# POWER.net
KiCad netlist of a schematic drawn in Altium Designer
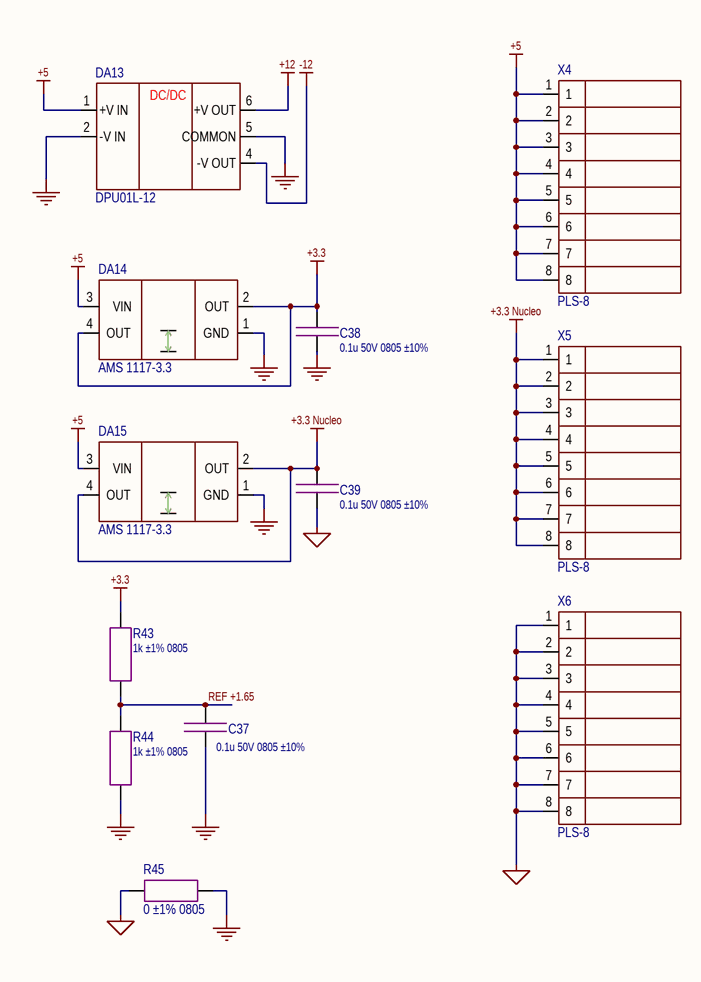
[diagram p0: POWER.SchDoc]

(export (version "E")
  (design (tool "Eeschema 10.0.6"))
  (components
    (comp (ref "C37")
      (value "0.1u 50V 0805 ±10%")
      (footprint "CAP: SMD 0805 MD IPC 782")
      (libsource (lib "UOMP capacitors") (part "0.1u 50V 0805 ±10%"))
    )
    (comp (ref "C38")
      (value "0.1u 50V 0805 ±10%")
      (footprint "CAP: SMD 0805 MD IPC 782")
      (libsource (lib "UOMP capacitors") (part "0.1u 50V 0805 ±10%"))
    )
    (comp (ref "C39")
      (value "0.1u 50V 0805 ±10%")
      (footprint "CAP: SMD 0805 MD IPC 782")
      (libsource (lib "UOMP capacitors") (part "0.1u 50V 0805 ±10%"))
    )
    (comp (ref "DA13")
      (value "DPU01L-12")
      (footprint "SIP-6")
      (libsource (lib "UOMP power") (part "DC-DC{colon} +12/-12V DPU01L-12"))
    )
    (comp (ref "DA14")
      (value "AMS 1117-3.3")
      (footprint "IC: SOT 223")
      (libsource (lib "UOMP power") (part "LDO{colon} 15-3.3V AMS1117"))
    )
    (comp (ref "DA15")
      (value "AMS 1117-3.3")
      (footprint "IC: SOT 223")
      (libsource (lib "UOMP power") (part "LDO{colon} 15-3.3V AMS1117"))
    )
    (comp (ref "R43")
      (value "1k ±1% 0805")
      (footprint "RES: SMD 0805 MD IPC 782")
      (libsource (lib "UOMP resistors") (part "1k ±1% 0805"))
    )
    (comp (ref "R44")
      (value "1k ±1% 0805")
      (footprint "RES: SMD 0805 MD IPC 782")
      (libsource (lib "UOMP resistors") (part "1k ±1% 0805"))
    )
    (comp (ref "R45")
      (value "0 ±1% 0805")
      (footprint "RES: SMD 0805 MD IPC 782")
      (libsource (lib "UOMP resistors") (part "0 ±1% 0805"))
    )
    (comp (ref "X4")
      (value "PLS-8")
      (footprint "CON: 8PIN PLS-8")
      (libsource (lib "UOMP connectors") (part "8 pin PLS 8"))
    )
    (comp (ref "X5")
      (value "PLS-8")
      (footprint "CON: 8PIN PLS-8")
      (libsource (lib "UOMP connectors") (part "8 pin PLS 8"))
    )
    (comp (ref "X6")
      (value "PLS-8")
      (footprint "CON: 8PIN PLS-8")
      (libsource (lib "UOMP connectors") (part "8 pin PLS 8"))
    )
  )
  (nets
    (net (code "1") (name "+3.3") (class "Default")
      (node (ref "C38") (pin "1") (pinfunction "1_1") (pintype "passive"))
      (node (ref "DA14") (pin "2") (pinfunction "OUT_2") (pintype "passive"))
      (node (ref "DA14") (pin "4") (pinfunction "OUT_4") (pintype "passive"))
      (node (ref "R43") (pin "2") (pinfunction "2_2") (pintype "passive"))
    )
    (net (code "2") (name "+3.3 Nucleo") (class "Default")
      (node (ref "C39") (pin "1") (pinfunction "1_1") (pintype "passive"))
      (node (ref "DA15") (pin "2") (pinfunction "OUT_2") (pintype "passive"))
      (node (ref "DA15") (pin "4") (pinfunction "OUT_4") (pintype "passive"))
      (node (ref "X5") (pin "1") (pinfunction "1_1") (pintype "passive"))
      (node (ref "X5") (pin "2") (pinfunction "2_2") (pintype "passive"))
      (node (ref "X5") (pin "3") (pinfunction "3_3") (pintype "passive"))
      (node (ref "X5") (pin "4") (pinfunction "4_4") (pintype "passive"))
      (node (ref "X5") (pin "5") (pinfunction "5_5") (pintype "passive"))
      (node (ref "X5") (pin "6") (pinfunction "6_6") (pintype "passive"))
      (node (ref "X5") (pin "7") (pinfunction "7_7") (pintype "passive"))
      (node (ref "X5") (pin "8") (pinfunction "8_8") (pintype "passive"))
    )
    (net (code "3") (name "+5") (class "Default")
      (node (ref "DA13") (pin "1") (pinfunction "+V_IN_1") (pintype "passive"))
      (node (ref "DA14") (pin "3") (pinfunction "VIN_3") (pintype "passive"))
      (node (ref "DA15") (pin "3") (pinfunction "VIN_3") (pintype "passive"))
      (node (ref "X4") (pin "1") (pinfunction "1_1") (pintype "passive"))
      (node (ref "X4") (pin "2") (pinfunction "2_2") (pintype "passive"))
      (node (ref "X4") (pin "3") (pinfunction "3_3") (pintype "passive"))
      (node (ref "X4") (pin "4") (pinfunction "4_4") (pintype "passive"))
      (node (ref "X4") (pin "5") (pinfunction "5_5") (pintype "passive"))
      (node (ref "X4") (pin "6") (pinfunction "6_6") (pintype "passive"))
      (node (ref "X4") (pin "7") (pinfunction "7_7") (pintype "passive"))
      (node (ref "X4") (pin "8") (pinfunction "8_8") (pintype "passive"))
    )
    (net (code "4") (name "+12") (class "Default")
      (node (ref "DA13") (pin "6") (pinfunction "+V_OUT_6") (pintype "passive"))
    )
    (net (code "5") (name "-12") (class "Default")
      (node (ref "DA13") (pin "4") (pinfunction "-V_OUT_4") (pintype "passive"))
    )
    (net (code "6") (name "/REF +1.65") (class "Default")
      (node (ref "C37") (pin "1") (pinfunction "1_1") (pintype "passive"))
      (node (ref "R43") (pin "1") (pinfunction "1_1") (pintype "passive"))
      (node (ref "R44") (pin "2") (pinfunction "2_2") (pintype "passive"))
    )
    (net (code "7") (name "GND") (class "Default")
      (node (ref "C37") (pin "2") (pinfunction "2_2") (pintype "passive"))
      (node (ref "C38") (pin "2") (pinfunction "2_2") (pintype "passive"))
      (node (ref "DA13") (pin "2") (pinfunction "-V_IN_2") (pintype "passive"))
      (node (ref "DA13") (pin "5") (pinfunction "COMMON_5") (pintype "passive"))
      (node (ref "DA14") (pin "1") (pinfunction "GND_1") (pintype "passive"))
      (node (ref "DA15") (pin "1") (pinfunction "GND_1") (pintype "passive"))
      (node (ref "R44") (pin "1") (pinfunction "1_1") (pintype "passive"))
      (node (ref "R45") (pin "2") (pinfunction "2_2") (pintype "passive"))
    )
    (net (code "8") (name "GNDD") (class "Default")
      (node (ref "C39") (pin "2") (pinfunction "2_2") (pintype "passive"))
      (node (ref "R45") (pin "1") (pinfunction "1_1") (pintype "passive"))
      (node (ref "X6") (pin "1") (pinfunction "1_1") (pintype "passive"))
      (node (ref "X6") (pin "2") (pinfunction "2_2") (pintype "passive"))
      (node (ref "X6") (pin "3") (pinfunction "3_3") (pintype "passive"))
      (node (ref "X6") (pin "4") (pinfunction "4_4") (pintype "passive"))
      (node (ref "X6") (pin "5") (pinfunction "5_5") (pintype "passive"))
      (node (ref "X6") (pin "6") (pinfunction "6_6") (pintype "passive"))
      (node (ref "X6") (pin "7") (pinfunction "7_7") (pintype "passive"))
      (node (ref "X6") (pin "8") (pinfunction "8_8") (pintype "passive"))
    )
  )
)
